# rpi-stack-lights.net
KiCad netlist of a schematic drawn in EAGLE
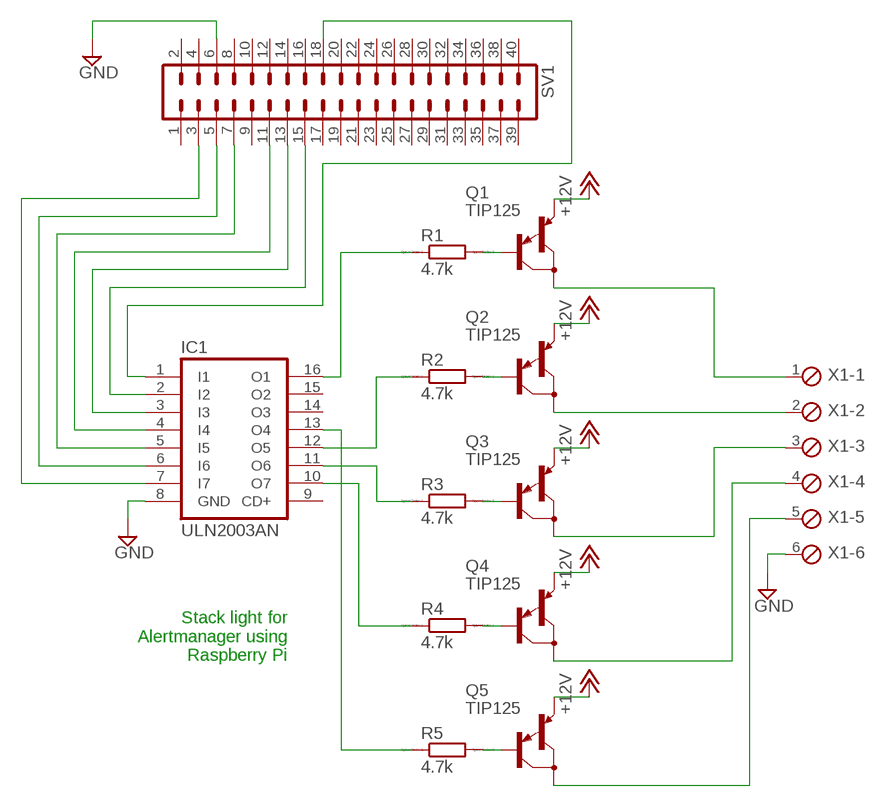
[diagram p0: schematic, sheet 1]

(export (version "E")
  (design (tool "Eeschema 10.0.6"))
  (components
    (comp (ref "IC1")
      (value "ULN2003AN")
      (footprint "eagle-import:DIL16")
      (libsource (lib "eagle-import") (part "ULN2003AN"))
    )
    (comp (ref "Q1")
      (value "TIP125")
      (footprint "eagle-import:TO220")
      (libsource (lib "eagle-import") (part "TIP125"))
    )
    (comp (ref "Q2")
      (value "TIP125")
      (footprint "eagle-import:TO220")
      (libsource (lib "eagle-import") (part "TIP125"))
    )
    (comp (ref "Q3")
      (value "TIP125")
      (footprint "eagle-import:TO220")
      (libsource (lib "eagle-import") (part "TIP125"))
    )
    (comp (ref "Q4")
      (value "TIP125")
      (footprint "eagle-import:TO220")
      (libsource (lib "eagle-import") (part "TIP125"))
    )
    (comp (ref "Q5")
      (value "TIP125")
      (footprint "eagle-import:TO220")
      (libsource (lib "eagle-import") (part "TIP125"))
    )
    (comp (ref "R1")
      (value "4.7k")
      (footprint "eagle-import:0204_7")
      (libsource (lib "eagle-import") (part "R0204/7"))
    )
    (comp (ref "R2")
      (value "4.7k")
      (footprint "eagle-import:0204_7")
      (libsource (lib "eagle-import") (part "R0204/7"))
    )
    (comp (ref "R3")
      (value "4.7k")
      (footprint "eagle-import:0204_7")
      (libsource (lib "eagle-import") (part "R0204/7"))
    )
    (comp (ref "R4")
      (value "4.7k")
      (footprint "eagle-import:0204_7")
      (libsource (lib "eagle-import") (part "R0204/7"))
    )
    (comp (ref "R5")
      (value "4.7k")
      (footprint "eagle-import:0204_7")
      (libsource (lib "eagle-import") (part "R0204/7"))
    )
    (comp (ref "SV1")
      (value "MA20-2")
      (footprint "eagle-import:MA20-2")
      (libsource (lib "eagle-import") (part "MA20-2"))
    )
    (comp (ref "X1")
      (value "MPT6")
      (footprint "eagle-import:6POL254")
      (libsource (lib "eagle-import") (part "MPT6"))
    )
  )
  (nets
    (net (code "1") (name "+12V") (class "Default")
      (node (ref "Q1") (pin "3") (pinfunction "E_3") (pintype "passive"))
      (node (ref "Q2") (pin "3") (pinfunction "E_3") (pintype "passive"))
      (node (ref "Q3") (pin "3") (pinfunction "E_3") (pintype "passive"))
      (node (ref "Q4") (pin "3") (pinfunction "E_3") (pintype "passive"))
      (node (ref "Q5") (pin "3") (pinfunction "E_3") (pintype "passive"))
    )
    (net (code "2") (name "GND") (class "Default")
      (node (ref "IC1") (pin "8") (pinfunction "GND_8") (pintype "power_in"))
      (node (ref "SV1") (pin "6") (pinfunction "6_6") (pintype "passive"))
      (node (ref "X1") (pin "6") (pinfunction "1_6") (pintype "passive"))
    )
    (net (code "3") (name "Net-(IC1-I1)") (class "Default")
      (node (ref "IC1") (pin "1") (pinfunction "I1_1") (pintype "input"))
      (node (ref "SV1") (pin "18") (pinfunction "18_18") (pintype "passive"))
    )
    (net (code "4") (name "Net-(IC1-I2)") (class "Default")
      (node (ref "IC1") (pin "2") (pinfunction "I2_2") (pintype "input"))
      (node (ref "SV1") (pin "15") (pinfunction "15_15") (pintype "passive"))
    )
    (net (code "5") (name "Net-(IC1-I3)") (class "Default")
      (node (ref "IC1") (pin "3") (pinfunction "I3_3") (pintype "input"))
      (node (ref "SV1") (pin "13") (pinfunction "13_13") (pintype "passive"))
    )
    (net (code "6") (name "Net-(IC1-I4)") (class "Default")
      (node (ref "IC1") (pin "4") (pinfunction "I4_4") (pintype "input"))
      (node (ref "SV1") (pin "11") (pinfunction "11_11") (pintype "passive"))
    )
    (net (code "7") (name "Net-(IC1-I5)") (class "Default")
      (node (ref "IC1") (pin "5") (pinfunction "I5_5") (pintype "input"))
      (node (ref "SV1") (pin "7") (pinfunction "7_7") (pintype "passive"))
    )
    (net (code "8") (name "Net-(IC1-I6)") (class "Default")
      (node (ref "IC1") (pin "6") (pinfunction "I6_6") (pintype "input"))
      (node (ref "SV1") (pin "5") (pinfunction "5_5") (pintype "passive"))
    )
    (net (code "9") (name "Net-(IC1-I7)") (class "Default")
      (node (ref "IC1") (pin "7") (pinfunction "I7_7") (pintype "input"))
      (node (ref "SV1") (pin "3") (pinfunction "3_3") (pintype "passive"))
    )
    (net (code "10") (name "Net-(IC1-O1)") (class "Default")
      (node (ref "IC1") (pin "16") (pinfunction "O1_16") (pintype "open_collector"))
      (node (ref "R1") (pin "1") (pinfunction "1_1") (pintype "passive"))
    )
    (net (code "11") (name "Net-(IC1-O4)") (class "Default")
      (node (ref "IC1") (pin "13") (pinfunction "O4_13") (pintype "open_collector"))
      (node (ref "R5") (pin "1") (pinfunction "1_1") (pintype "passive"))
    )
    (net (code "12") (name "Net-(IC1-O5)") (class "Default")
      (node (ref "IC1") (pin "12") (pinfunction "O5_12") (pintype "open_collector"))
      (node (ref "R2") (pin "1") (pinfunction "1_1") (pintype "passive"))
    )
    (net (code "13") (name "Net-(IC1-O6)") (class "Default")
      (node (ref "IC1") (pin "11") (pinfunction "O6_11") (pintype "open_collector"))
      (node (ref "R3") (pin "1") (pinfunction "1_1") (pintype "passive"))
    )
    (net (code "14") (name "Net-(IC1-O7)") (class "Default")
      (node (ref "IC1") (pin "10") (pinfunction "O7_10") (pintype "open_collector"))
      (node (ref "R4") (pin "1") (pinfunction "1_1") (pintype "passive"))
    )
    (net (code "15") (name "Net-(Q1-B)") (class "Default")
      (node (ref "Q1") (pin "1") (pinfunction "B_1") (pintype "passive"))
      (node (ref "R1") (pin "2") (pinfunction "2_2") (pintype "passive"))
    )
    (net (code "16") (name "Net-(Q1-C)") (class "Default")
      (node (ref "Q1") (pin "2") (pinfunction "C_2") (pintype "passive"))
      (node (ref "X1") (pin "1") (pinfunction "1_1") (pintype "passive"))
    )
    (net (code "17") (name "Net-(Q2-B)") (class "Default")
      (node (ref "Q2") (pin "1") (pinfunction "B_1") (pintype "passive"))
      (node (ref "R2") (pin "2") (pinfunction "2_2") (pintype "passive"))
    )
    (net (code "18") (name "Net-(Q2-C)") (class "Default")
      (node (ref "Q2") (pin "2") (pinfunction "C_2") (pintype "passive"))
      (node (ref "X1") (pin "2") (pinfunction "1_2") (pintype "passive"))
    )
    (net (code "19") (name "Net-(Q3-B)") (class "Default")
      (node (ref "Q3") (pin "1") (pinfunction "B_1") (pintype "passive"))
      (node (ref "R3") (pin "2") (pinfunction "2_2") (pintype "passive"))
    )
    (net (code "20") (name "Net-(Q3-C)") (class "Default")
      (node (ref "Q3") (pin "2") (pinfunction "C_2") (pintype "passive"))
      (node (ref "X1") (pin "3") (pinfunction "1_3") (pintype "passive"))
    )
    (net (code "21") (name "Net-(Q4-B)") (class "Default")
      (node (ref "Q4") (pin "1") (pinfunction "B_1") (pintype "passive"))
      (node (ref "R4") (pin "2") (pinfunction "2_2") (pintype "passive"))
    )
    (net (code "22") (name "Net-(Q4-C)") (class "Default")
      (node (ref "Q4") (pin "2") (pinfunction "C_2") (pintype "passive"))
      (node (ref "X1") (pin "4") (pinfunction "1_4") (pintype "passive"))
    )
    (net (code "23") (name "Net-(Q5-B)") (class "Default")
      (node (ref "Q5") (pin "1") (pinfunction "B_1") (pintype "passive"))
      (node (ref "R5") (pin "2") (pinfunction "2_2") (pintype "passive"))
    )
    (net (code "24") (name "Net-(Q5-C)") (class "Default")
      (node (ref "Q5") (pin "2") (pinfunction "C_2") (pintype "passive"))
      (node (ref "X1") (pin "5") (pinfunction "1_5") (pintype "passive"))
    )
    (net (code "25") (name "unconnected-(IC1-CD+-Pad9)") (class "Default")
      (node (ref "IC1") (pin "9") (pinfunction "CD+_9") (pintype "passive"))
    )
    (net (code "26") (name "unconnected-(IC1-O2-Pad15)") (class "Default")
      (node (ref "IC1") (pin "15") (pinfunction "O2_15") (pintype "open_collector"))
    )
    (net (code "27") (name "unconnected-(IC1-O3-Pad14)") (class "Default")
      (node (ref "IC1") (pin "14") (pinfunction "O3_14") (pintype "open_collector"))
    )
    (net (code "28") (name "unconnected-(SV1-Pad1)") (class "Default")
      (node (ref "SV1") (pin "1") (pinfunction "1_1") (pintype "passive"))
    )
    (net (code "29") (name "unconnected-(SV1-Pad2)") (class "Default")
      (node (ref "SV1") (pin "2") (pinfunction "2_2") (pintype "passive"))
    )
    (net (code "30") (name "unconnected-(SV1-Pad4)") (class "Default")
      (node (ref "SV1") (pin "4") (pinfunction "4_4") (pintype "passive"))
    )
    (net (code "31") (name "unconnected-(SV1-Pad8)") (class "Default")
      (node (ref "SV1") (pin "8") (pinfunction "8_8") (pintype "passive"))
    )
    (net (code "32") (name "unconnected-(SV1-Pad9)") (class "Default")
      (node (ref "SV1") (pin "9") (pinfunction "9_9") (pintype "passive"))
    )
    (net (code "33") (name "unconnected-(SV1-Pad10)") (class "Default")
      (node (ref "SV1") (pin "10") (pinfunction "10_10") (pintype "passive"))
    )
    (net (code "34") (name "unconnected-(SV1-Pad12)") (class "Default")
      (node (ref "SV1") (pin "12") (pinfunction "12_12") (pintype "passive"))
    )
    (net (code "35") (name "unconnected-(SV1-Pad14)") (class "Default")
      (node (ref "SV1") (pin "14") (pinfunction "14_14") (pintype "passive"))
    )
    (net (code "36") (name "unconnected-(SV1-Pad16)") (class "Default")
      (node (ref "SV1") (pin "16") (pinfunction "16_16") (pintype "passive"))
    )
    (net (code "37") (name "unconnected-(SV1-Pad17)") (class "Default")
      (node (ref "SV1") (pin "17") (pinfunction "17_17") (pintype "passive"))
    )
    (net (code "38") (name "unconnected-(SV1-Pad19)") (class "Default")
      (node (ref "SV1") (pin "19") (pinfunction "19_19") (pintype "passive"))
    )
    (net (code "39") (name "unconnected-(SV1-Pad20)") (class "Default")
      (node (ref "SV1") (pin "20") (pinfunction "20_20") (pintype "passive"))
    )
    (net (code "40") (name "unconnected-(SV1-Pad21)") (class "Default")
      (node (ref "SV1") (pin "21") (pinfunction "21_21") (pintype "passive"))
    )
    (net (code "41") (name "unconnected-(SV1-Pad22)") (class "Default")
      (node (ref "SV1") (pin "22") (pinfunction "22_22") (pintype "passive"))
    )
    (net (code "42") (name "unconnected-(SV1-Pad23)") (class "Default")
      (node (ref "SV1") (pin "23") (pinfunction "23_23") (pintype "passive"))
    )
    (net (code "43") (name "unconnected-(SV1-Pad24)") (class "Default")
      (node (ref "SV1") (pin "24") (pinfunction "24_24") (pintype "passive"))
    )
    (net (code "44") (name "unconnected-(SV1-Pad25)") (class "Default")
      (node (ref "SV1") (pin "25") (pinfunction "25_25") (pintype "passive"))
    )
    (net (code "45") (name "unconnected-(SV1-Pad26)") (class "Default")
      (node (ref "SV1") (pin "26") (pinfunction "26_26") (pintype "passive"))
    )
    (net (code "46") (name "unconnected-(SV1-Pad27)") (class "Default")
      (node (ref "SV1") (pin "27") (pinfunction "27_27") (pintype "passive"))
    )
    (net (code "47") (name "unconnected-(SV1-Pad28)") (class "Default")
      (node (ref "SV1") (pin "28") (pinfunction "28_28") (pintype "passive"))
    )
    (net (code "48") (name "unconnected-(SV1-Pad29)") (class "Default")
      (node (ref "SV1") (pin "29") (pinfunction "29_29") (pintype "passive"))
    )
    (net (code "49") (name "unconnected-(SV1-Pad30)") (class "Default")
      (node (ref "SV1") (pin "30") (pinfunction "30_30") (pintype "passive"))
    )
    (net (code "50") (name "unconnected-(SV1-Pad31)") (class "Default")
      (node (ref "SV1") (pin "31") (pinfunction "31_31") (pintype "passive"))
    )
    (net (code "51") (name "unconnected-(SV1-Pad32)") (class "Default")
      (node (ref "SV1") (pin "32") (pinfunction "32_32") (pintype "passive"))
    )
    (net (code "52") (name "unconnected-(SV1-Pad33)") (class "Default")
      (node (ref "SV1") (pin "33") (pinfunction "33_33") (pintype "passive"))
    )
    (net (code "53") (name "unconnected-(SV1-Pad34)") (class "Default")
      (node (ref "SV1") (pin "34") (pinfunction "34_34") (pintype "passive"))
    )
    (net (code "54") (name "unconnected-(SV1-Pad35)") (class "Default")
      (node (ref "SV1") (pin "35") (pinfunction "35_35") (pintype "passive"))
    )
    (net (code "55") (name "unconnected-(SV1-Pad36)") (class "Default")
      (node (ref "SV1") (pin "36") (pinfunction "36_36") (pintype "passive"))
    )
    (net (code "56") (name "unconnected-(SV1-Pad37)") (class "Default")
      (node (ref "SV1") (pin "37") (pinfunction "37_37") (pintype "passive"))
    )
    (net (code "57") (name "unconnected-(SV1-Pad38)") (class "Default")
      (node (ref "SV1") (pin "38") (pinfunction "38_38") (pintype "passive"))
    )
    (net (code "58") (name "unconnected-(SV1-Pad39)") (class "Default")
      (node (ref "SV1") (pin "39") (pinfunction "39_39") (pintype "passive"))
    )
    (net (code "59") (name "unconnected-(SV1-Pad40)") (class "Default")
      (node (ref "SV1") (pin "40") (pinfunction "40_40") (pintype "passive"))
    )
  )
)
